# Drofnats.net
KiCad netlist of a schematic drawn in Altium Designer
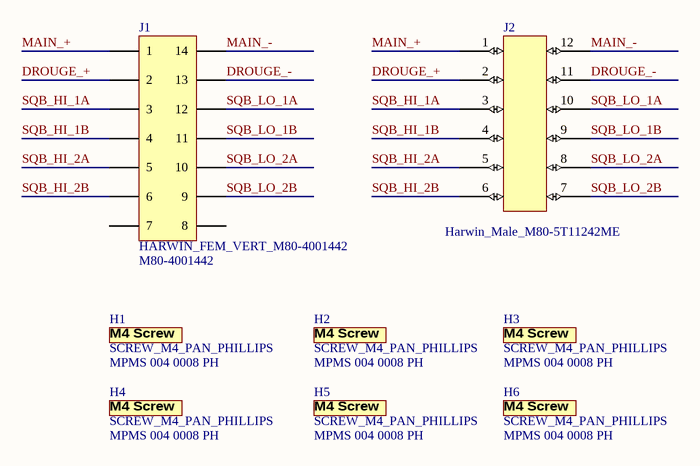
[diagram p0: Drofnats.SchDoc]

(export (version "E")
  (design (tool "Eeschema 10.0.6"))
  (components
    (comp (ref "H1")
      (value "SCREW_M4_PAN_PHILLIPS")
      (footprint "SCREW_M4")
      (description "MACHINE SCREW PAN PHILLIPS M4")
      (fields
        (field (name "MANUFACTURER") "B&F Fastener Supply")
        (field (name "MANUFACTURER PART NUMBER") "MPMS 004 0008 PH")
      )
      (libsource (lib "Stanford Student Space Initiative") (part "SCREW_M4_PAN_PHILLIPS"))
    )
    (comp (ref "H2")
      (value "SCREW_M4_PAN_PHILLIPS")
      (footprint "SCREW_M4")
      (description "MACHINE SCREW PAN PHILLIPS M4")
      (fields
        (field (name "MANUFACTURER") "B&F Fastener Supply")
        (field (name "MANUFACTURER PART NUMBER") "MPMS 004 0008 PH")
      )
      (libsource (lib "Stanford Student Space Initiative") (part "SCREW_M4_PAN_PHILLIPS"))
    )
    (comp (ref "H3")
      (value "SCREW_M4_PAN_PHILLIPS")
      (footprint "SCREW_M4")
      (description "MACHINE SCREW PAN PHILLIPS M4")
      (fields
        (field (name "MANUFACTURER") "B&F Fastener Supply")
        (field (name "MANUFACTURER PART NUMBER") "MPMS 004 0008 PH")
      )
      (libsource (lib "Stanford Student Space Initiative") (part "SCREW_M4_PAN_PHILLIPS"))
    )
    (comp (ref "H4")
      (value "SCREW_M4_PAN_PHILLIPS")
      (footprint "SCREW_M4")
      (description "MACHINE SCREW PAN PHILLIPS M4")
      (fields
        (field (name "MANUFACTURER") "B&F Fastener Supply")
        (field (name "MANUFACTURER PART NUMBER") "MPMS 004 0008 PH")
      )
      (libsource (lib "Stanford Student Space Initiative") (part "SCREW_M4_PAN_PHILLIPS"))
    )
    (comp (ref "H5")
      (value "SCREW_M4_PAN_PHILLIPS")
      (footprint "SCREW_M4")
      (description "MACHINE SCREW PAN PHILLIPS M4")
      (fields
        (field (name "MANUFACTURER") "B&F Fastener Supply")
        (field (name "MANUFACTURER PART NUMBER") "MPMS 004 0008 PH")
      )
      (libsource (lib "Stanford Student Space Initiative") (part "SCREW_M4_PAN_PHILLIPS"))
    )
    (comp (ref "H6")
      (value "SCREW_M4_PAN_PHILLIPS")
      (footprint "SCREW_M4")
      (description "MACHINE SCREW PAN PHILLIPS M4")
      (fields
        (field (name "MANUFACTURER") "B&F Fastener Supply")
        (field (name "MANUFACTURER PART NUMBER") "MPMS 004 0008 PH")
      )
      (libsource (lib "Stanford Student Space Initiative") (part "SCREW_M4_PAN_PHILLIPS"))
    )
    (comp (ref "J1")
      (value "HARWIN_FEM_VERT_M80-4001442")
      (footprint "HARWIN_M80-4001442")
      (description "7+7 POS FEM +J/S 3mm TAIL TIN")
      (fields (field (name "MANUFACTURER PART NUMBER") "M80-4001442") (field (name "MANUFACTURER") "Harwin"))
      (libsource (lib "Stanford Student Space Initiative") (part "Symbol"))
    )
    (comp (ref "J2")
      (value "Harwin M80-5T11242ME")
      (footprint "HARWIN-M80-5T11242ME")
      (description "6+6 Pos. Male DIL Vertical Throughboard Conn. 101Lok")
      (libsource (lib "Stanford Student Space Initiative") (part "Harwin M80-5T11242ME-Symbol-1"))
    )
  )
  (nets
    (net (code "1") (name "/DROUGE_+") (class "Default")
      (node (ref "J1") (pin "2") (pinfunction "2_2") (pintype "passive"))
      (node (ref "J2") (pin "2") (pintype "bidirectional"))
    )
    (net (code "2") (name "/DROUGE_-") (class "Default")
      (node (ref "J1") (pin "13") (pinfunction "13_13") (pintype "passive"))
      (node (ref "J2") (pin "11") (pintype "bidirectional"))
    )
    (net (code "3") (name "/MAIN_+") (class "Default")
      (node (ref "J1") (pin "1") (pinfunction "1_1") (pintype "passive"))
      (node (ref "J2") (pin "1") (pintype "bidirectional"))
    )
    (net (code "4") (name "/MAIN_-") (class "Default")
      (node (ref "J1") (pin "14") (pinfunction "14_14") (pintype "passive"))
      (node (ref "J2") (pin "12") (pintype "bidirectional"))
    )
    (net (code "5") (name "/SQB_HI_1A") (class "Default")
      (node (ref "J1") (pin "3") (pinfunction "3_3") (pintype "passive"))
      (node (ref "J2") (pin "3") (pintype "bidirectional"))
    )
    (net (code "6") (name "/SQB_HI_1B") (class "Default")
      (node (ref "J1") (pin "4") (pinfunction "4_4") (pintype "passive"))
      (node (ref "J2") (pin "4") (pintype "bidirectional"))
    )
    (net (code "7") (name "/SQB_HI_2A") (class "Default")
      (node (ref "J1") (pin "5") (pinfunction "5_5") (pintype "passive"))
      (node (ref "J2") (pin "5") (pintype "bidirectional"))
    )
    (net (code "8") (name "/SQB_HI_2B") (class "Default")
      (node (ref "J1") (pin "6") (pinfunction "6_6") (pintype "passive"))
      (node (ref "J2") (pin "6") (pintype "bidirectional"))
    )
    (net (code "9") (name "/SQB_LO_1A") (class "Default")
      (node (ref "J1") (pin "12") (pinfunction "12_12") (pintype "passive"))
      (node (ref "J2") (pin "10") (pintype "bidirectional"))
    )
    (net (code "10") (name "/SQB_LO_1B") (class "Default")
      (node (ref "J1") (pin "11") (pinfunction "11_11") (pintype "passive"))
      (node (ref "J2") (pin "9") (pintype "bidirectional"))
    )
    (net (code "11") (name "/SQB_LO_2A") (class "Default")
      (node (ref "J1") (pin "10") (pinfunction "10_10") (pintype "passive"))
      (node (ref "J2") (pin "8") (pintype "bidirectional"))
    )
    (net (code "12") (name "/SQB_LO_2B") (class "Default")
      (node (ref "J1") (pin "9") (pinfunction "9_9") (pintype "passive"))
      (node (ref "J2") (pin "7") (pintype "bidirectional"))
    )
    (net (code "13") (name "unconnected-(J1-Pad7)") (class "Default")
      (node (ref "J1") (pin "7") (pinfunction "7_7") (pintype "passive"))
    )
    (net (code "14") (name "unconnected-(J1-Pad8)") (class "Default")
      (node (ref "J1") (pin "8") (pinfunction "8_8") (pintype "passive"))
    )
  )
)
